# current_sense.net
KiCad netlist of a schematic drawn in EAGLE
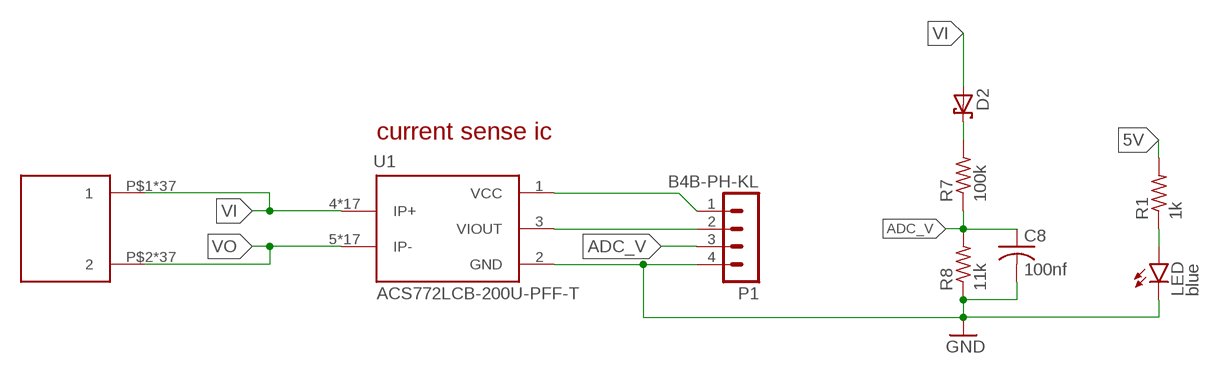
[diagram p0: schematic, sheet 1]

(export (version "E")
  (design (tool "Eeschema 10.0.6"))
  (components
    (comp (ref "C8")
      (value "100nf")
      (footprint "eagle-import:C0805")
      (libsource (lib "eagle-import") (part "C-USC0805"))
    )
    (comp (ref "D2")
      (value "1PS76SB70,115")
      (footprint "eagle-import:SOD323(F)")
      (fields (field (name "MF") "Nexperia USA"))
      (libsource (lib "eagle-import") (part "1PS76SB70,115"))
    )
    (comp (ref "LED")
      (value "blue")
      (footprint "eagle-import:CHIPLED_0805")
      (libsource (lib "eagle-import") (part "LEDCHIPLED_0805"))
    )
    (comp (ref "P1")
      (value "B4B-PH-KL")
      (footprint "eagle-import:B4B-PH-K-S")
      (libsource (lib "eagle-import") (part "B4B-PH-KL"))
    )
    (comp (ref "R1")
      (value "1k")
      (footprint "eagle-import:R0805")
      (libsource (lib "eagle-import") (part "R-US_R0805"))
    )
    (comp (ref "R7")
      (value "100k")
      (footprint "eagle-import:R0805")
      (libsource (lib "eagle-import") (part "R-US_R0805"))
    )
    (comp (ref "R8")
      (value "11k")
      (footprint "eagle-import:R0805")
      (libsource (lib "eagle-import") (part "R-US_R0805"))
    )
    (comp (ref "U$1")
      (value "CON_PAD")
      (footprint "eagle-import:CON_PAD")
      (libsource (lib "eagle-import") (part "CON_PAD"))
    )
    (comp (ref "U1")
      (value "ACS772LCB-200U-PFF-T")
      (footprint "eagle-import:XDCR_ACS772LCB-100U-PFF-T")
      (fields (field (name "MF") "Allegro MicroSystems LLC") (field (name "MP") "ACS772LCB-100U-PFF-T"))
      (libsource (lib "eagle-import") (part "ACS772LCB-100U-PFF-T"))
    )
  )
  (nets
    (net (code "1") (name "5V") (class "Default")
      (node (ref "P1") (pin "1") (pinfunction "1_1") (pintype "passive"))
      (node (ref "R1") (pin "2") (pinfunction "2_2") (pintype "passive"))
      (node (ref "U1") (pin "1") (pinfunction "VCC_1") (pintype "power_in"))
    )
    (net (code "2") (name "ADC_V") (class "Default")
      (node (ref "C8") (pin "1") (pinfunction "1_1") (pintype "passive"))
      (node (ref "P1") (pin "3") (pinfunction "3_3") (pintype "passive"))
      (node (ref "R7") (pin "1") (pinfunction "1_1") (pintype "passive"))
      (node (ref "R8") (pin "2") (pinfunction "2_2") (pintype "passive"))
    )
    (net (code "3") (name "GND") (class "Default")
      (node (ref "C8") (pin "2") (pinfunction "2_2") (pintype "passive"))
      (node (ref "LED") (pin "C") (pinfunction "C_C") (pintype "passive"))
      (node (ref "P1") (pin "4") (pinfunction "4_4") (pintype "passive"))
      (node (ref "R8") (pin "1") (pinfunction "1_1") (pintype "passive"))
      (node (ref "U1") (pin "2") (pinfunction "GND_2") (pintype "power_in"))
    )
    (net (code "4") (name "Net-(D2-K)") (class "Default")
      (node (ref "D2") (pin "1") (pinfunction "K_1") (pintype "passive"))
      (node (ref "R7") (pin "2") (pinfunction "2_2") (pintype "passive"))
    )
    (net (code "5") (name "Net-(LED-PadA)") (class "Default")
      (node (ref "LED") (pin "A") (pinfunction "A_A") (pintype "passive"))
      (node (ref "R1") (pin "1") (pinfunction "1_1") (pintype "passive"))
    )
    (net (code "6") (name "Net-(U1-VIOUT)") (class "Default")
      (node (ref "P1") (pin "2") (pinfunction "2_2") (pintype "passive"))
      (node (ref "U1") (pin "3") (pinfunction "VIOUT_3") (pintype "output"))
    )
    (net (code "7") (name "VI") (class "Default")
      (node (ref "D2") (pin "2") (pinfunction "A_2") (pintype "passive"))
      (node (ref "U$1") (pin "P$1") (pinfunction "1_P$1") (pintype "bidirectional"))
      (node (ref "U$1") (pin "P$10") (pinfunction "1_P$10") (pintype "bidirectional"))
      (node (ref "U$1") (pin "P$11") (pinfunction "1_P$11") (pintype "bidirectional"))
      (node (ref "U$1") (pin "P$12") (pinfunction "1_P$12") (pintype "bidirectional"))
      (node (ref "U$1") (pin "P$13") (pinfunction "1_P$13") (pintype "bidirectional"))
      (node (ref "U$1") (pin "P$14") (pinfunction "1_P$14") (pintype "bidirectional"))
      (node (ref "U$1") (pin "P$15") (pinfunction "1_P$15") (pintype "bidirectional"))
      (node (ref "U$1") (pin "P$16") (pinfunction "1_P$16") (pintype "bidirectional"))
      (node (ref "U$1") (pin "P$17") (pinfunction "1_P$17") (pintype "bidirectional"))
      (node (ref "U$1") (pin "P$18") (pinfunction "1_P$18") (pintype "bidirectional"))
      (node (ref "U$1") (pin "P$19") (pinfunction "1_P$19") (pintype "bidirectional"))
      (node (ref "U$1") (pin "P$20") (pinfunction "1_P$20") (pintype "bidirectional"))
      (node (ref "U$1") (pin "P$21") (pinfunction "1_P$21") (pintype "bidirectional"))
      (node (ref "U$1") (pin "P$22") (pinfunction "1_P$22") (pintype "bidirectional"))
      (node (ref "U$1") (pin "P$23") (pinfunction "1_P$23") (pintype "bidirectional"))
      (node (ref "U$1") (pin "P$24") (pinfunction "1_P$24") (pintype "bidirectional"))
      (node (ref "U$1") (pin "P$25") (pinfunction "1_P$25") (pintype "bidirectional"))
      (node (ref "U$1") (pin "P$26") (pinfunction "1_P$26") (pintype "bidirectional"))
      (node (ref "U$1") (pin "P$27") (pinfunction "1_P$27") (pintype "bidirectional"))
      (node (ref "U$1") (pin "P$28") (pinfunction "1_P$28") (pintype "bidirectional"))
      (node (ref "U$1") (pin "P$29") (pinfunction "1_P$29") (pintype "bidirectional"))
      (node (ref "U$1") (pin "P$3") (pinfunction "1_P$3") (pintype "bidirectional"))
      (node (ref "U$1") (pin "P$30") (pinfunction "1_P$30") (pintype "bidirectional"))
      (node (ref "U$1") (pin "P$31") (pinfunction "1_P$31") (pintype "bidirectional"))
      (node (ref "U$1") (pin "P$32") (pinfunction "1_P$32") (pintype "bidirectional"))
      (node (ref "U$1") (pin "P$33") (pinfunction "1_P$33") (pintype "bidirectional"))
      (node (ref "U$1") (pin "P$34") (pinfunction "1_P$34") (pintype "bidirectional"))
      (node (ref "U$1") (pin "P$35") (pinfunction "1_P$35") (pintype "bidirectional"))
      (node (ref "U$1") (pin "P$36") (pinfunction "1_P$36") (pintype "bidirectional"))
      (node (ref "U$1") (pin "P$37") (pinfunction "1_P$37") (pintype "bidirectional"))
      (node (ref "U$1") (pin "P$38") (pinfunction "1_P$38") (pintype "bidirectional"))
      (node (ref "U$1") (pin "P$39") (pinfunction "1_P$39") (pintype "bidirectional"))
      (node (ref "U$1") (pin "P$5") (pinfunction "1_P$5") (pintype "bidirectional"))
      (node (ref "U$1") (pin "P$6") (pinfunction "1_P$6") (pintype "bidirectional"))
      (node (ref "U$1") (pin "P$7") (pinfunction "1_P$7") (pintype "bidirectional"))
      (node (ref "U$1") (pin "P$8") (pinfunction "1_P$8") (pintype "bidirectional"))
      (node (ref "U$1") (pin "P$9") (pinfunction "1_P$9") (pintype "bidirectional"))
      (node (ref "U1") (pin "4") (pinfunction "IP+_4") (pintype "passive"))
      (node (ref "U1") (pin "4_1") (pinfunction "IP+_4_1") (pintype "passive"))
      (node (ref "U1") (pin "4_10") (pinfunction "IP+_4_10") (pintype "passive"))
      (node (ref "U1") (pin "4_11") (pinfunction "IP+_4_11") (pintype "passive"))
      (node (ref "U1") (pin "4_12") (pinfunction "IP+_4_12") (pintype "passive"))
      (node (ref "U1") (pin "4_13") (pinfunction "IP+_4_13") (pintype "passive"))
      (node (ref "U1") (pin "4_14") (pinfunction "IP+_4_14") (pintype "passive"))
      (node (ref "U1") (pin "4_15") (pinfunction "IP+_4_15") (pintype "passive"))
      (node (ref "U1") (pin "4_16") (pinfunction "IP+_4_16") (pintype "passive"))
      (node (ref "U1") (pin "4_2") (pinfunction "IP+_4_2") (pintype "passive"))
      (node (ref "U1") (pin "4_3") (pinfunction "IP+_4_3") (pintype "passive"))
      (node (ref "U1") (pin "4_4") (pinfunction "IP+_4_4") (pintype "passive"))
      (node (ref "U1") (pin "4_5") (pinfunction "IP+_4_5") (pintype "passive"))
      (node (ref "U1") (pin "4_6") (pinfunction "IP+_4_6") (pintype "passive"))
      (node (ref "U1") (pin "4_7") (pinfunction "IP+_4_7") (pintype "passive"))
      (node (ref "U1") (pin "4_8") (pinfunction "IP+_4_8") (pintype "passive"))
      (node (ref "U1") (pin "4_9") (pinfunction "IP+_4_9") (pintype "passive"))
    )
    (net (code "8") (name "VO") (class "Default")
      (node (ref "U$1") (pin "P$2") (pinfunction "2_P$2") (pintype "bidirectional"))
      (node (ref "U$1") (pin "P$4") (pinfunction "2_P$4") (pintype "bidirectional"))
      (node (ref "U$1") (pin "P$40") (pinfunction "2_P$40") (pintype "bidirectional"))
      (node (ref "U$1") (pin "P$41") (pinfunction "2_P$41") (pintype "bidirectional"))
      (node (ref "U$1") (pin "P$42") (pinfunction "2_P$42") (pintype "bidirectional"))
      (node (ref "U$1") (pin "P$43") (pinfunction "2_P$43") (pintype "bidirectional"))
      (node (ref "U$1") (pin "P$44") (pinfunction "2_P$44") (pintype "bidirectional"))
      (node (ref "U$1") (pin "P$45") (pinfunction "2_P$45") (pintype "bidirectional"))
      (node (ref "U$1") (pin "P$46") (pinfunction "2_P$46") (pintype "bidirectional"))
      (node (ref "U$1") (pin "P$47") (pinfunction "2_P$47") (pintype "bidirectional"))
      (node (ref "U$1") (pin "P$48") (pinfunction "2_P$48") (pintype "bidirectional"))
      (node (ref "U$1") (pin "P$49") (pinfunction "2_P$49") (pintype "bidirectional"))
      (node (ref "U$1") (pin "P$50") (pinfunction "2_P$50") (pintype "bidirectional"))
      (node (ref "U$1") (pin "P$51") (pinfunction "2_P$51") (pintype "bidirectional"))
      (node (ref "U$1") (pin "P$52") (pinfunction "2_P$52") (pintype "bidirectional"))
      (node (ref "U$1") (pin "P$53") (pinfunction "2_P$53") (pintype "bidirectional"))
      (node (ref "U$1") (pin "P$54") (pinfunction "2_P$54") (pintype "bidirectional"))
      (node (ref "U$1") (pin "P$55") (pinfunction "2_P$55") (pintype "bidirectional"))
      (node (ref "U$1") (pin "P$56") (pinfunction "2_P$56") (pintype "bidirectional"))
      (node (ref "U$1") (pin "P$57") (pinfunction "2_P$57") (pintype "bidirectional"))
      (node (ref "U$1") (pin "P$58") (pinfunction "2_P$58") (pintype "bidirectional"))
      (node (ref "U$1") (pin "P$59") (pinfunction "2_P$59") (pintype "bidirectional"))
      (node (ref "U$1") (pin "P$60") (pinfunction "2_P$60") (pintype "bidirectional"))
      (node (ref "U$1") (pin "P$61") (pinfunction "2_P$61") (pintype "bidirectional"))
      (node (ref "U$1") (pin "P$62") (pinfunction "2_P$62") (pintype "bidirectional"))
      (node (ref "U$1") (pin "P$63") (pinfunction "2_P$63") (pintype "bidirectional"))
      (node (ref "U$1") (pin "P$64") (pinfunction "2_P$64") (pintype "bidirectional"))
      (node (ref "U$1") (pin "P$65") (pinfunction "2_P$65") (pintype "bidirectional"))
      (node (ref "U$1") (pin "P$66") (pinfunction "2_P$66") (pintype "bidirectional"))
      (node (ref "U$1") (pin "P$67") (pinfunction "2_P$67") (pintype "bidirectional"))
      (node (ref "U$1") (pin "P$68") (pinfunction "2_P$68") (pintype "bidirectional"))
      (node (ref "U$1") (pin "P$69") (pinfunction "2_P$69") (pintype "bidirectional"))
      (node (ref "U$1") (pin "P$70") (pinfunction "2_P$70") (pintype "bidirectional"))
      (node (ref "U$1") (pin "P$71") (pinfunction "2_P$71") (pintype "bidirectional"))
      (node (ref "U$1") (pin "P$72") (pinfunction "2_P$72") (pintype "bidirectional"))
      (node (ref "U$1") (pin "P$73") (pinfunction "2_P$73") (pintype "bidirectional"))
      (node (ref "U$1") (pin "P$74") (pinfunction "2_P$74") (pintype "bidirectional"))
      (node (ref "U1") (pin "5") (pinfunction "IP-_5") (pintype "passive"))
      (node (ref "U1") (pin "5_1") (pinfunction "IP-_5_1") (pintype "passive"))
      (node (ref "U1") (pin "5_10") (pinfunction "IP-_5_10") (pintype "passive"))
      (node (ref "U1") (pin "5_11") (pinfunction "IP-_5_11") (pintype "passive"))
      (node (ref "U1") (pin "5_12") (pinfunction "IP-_5_12") (pintype "passive"))
      (node (ref "U1") (pin "5_13") (pinfunction "IP-_5_13") (pintype "passive"))
      (node (ref "U1") (pin "5_14") (pinfunction "IP-_5_14") (pintype "passive"))
      (node (ref "U1") (pin "5_15") (pinfunction "IP-_5_15") (pintype "passive"))
      (node (ref "U1") (pin "5_16") (pinfunction "IP-_5_16") (pintype "passive"))
      (node (ref "U1") (pin "5_2") (pinfunction "IP-_5_2") (pintype "passive"))
      (node (ref "U1") (pin "5_3") (pinfunction "IP-_5_3") (pintype "passive"))
      (node (ref "U1") (pin "5_4") (pinfunction "IP-_5_4") (pintype "passive"))
      (node (ref "U1") (pin "5_5") (pinfunction "IP-_5_5") (pintype "passive"))
      (node (ref "U1") (pin "5_6") (pinfunction "IP-_5_6") (pintype "passive"))
      (node (ref "U1") (pin "5_7") (pinfunction "IP-_5_7") (pintype "passive"))
      (node (ref "U1") (pin "5_8") (pinfunction "IP-_5_8") (pintype "passive"))
      (node (ref "U1") (pin "5_9") (pinfunction "IP-_5_9") (pintype "passive"))
    )
  )
)
